# disp.net
KiCad netlist of a schematic drawn in EAGLE
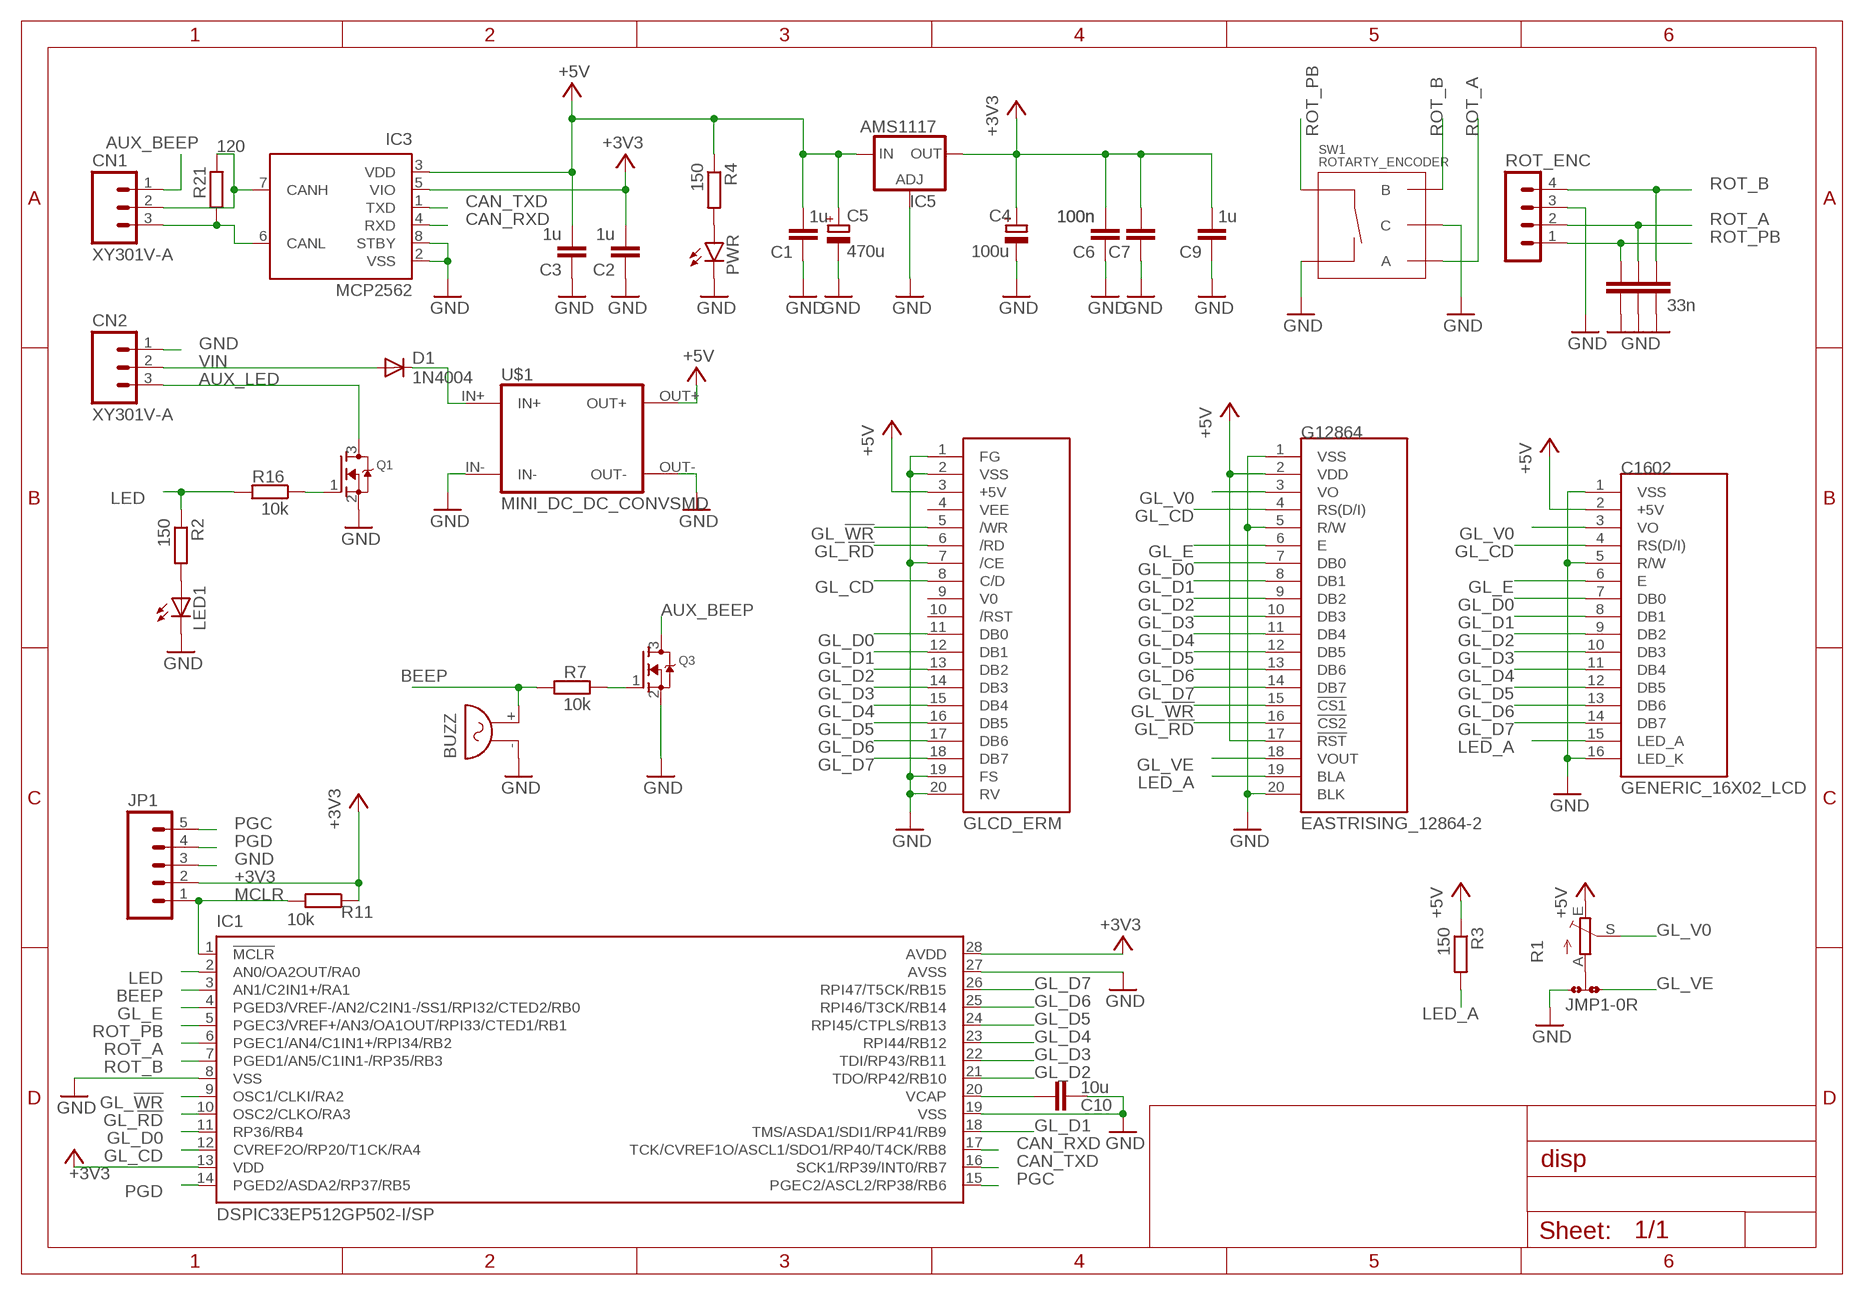
[diagram p0: schematic, sheet 1]

(export (version "E")
  (design (tool "Eeschema 10.0.6"))
  (components
    (comp (ref "BUZZ")
      (value "F/QMX")
      (footprint "eagle-import:F_QMX")
      (libsource (lib "eagle-import") (part "F/QMX"))
    )
    (comp (ref "C1")
      (value "1u")
      (footprint "eagle-import:C0603K")
      (libsource (lib "eagle-import") (part "C-EUC0603K"))
    )
    (comp (ref "C2")
      (value "1u")
      (footprint "eagle-import:C0603K")
      (libsource (lib "eagle-import") (part "C-EUC0603K"))
    )
    (comp (ref "C3")
      (value "1u")
      (footprint "eagle-import:C0603K")
      (libsource (lib "eagle-import") (part "C-EUC0603K"))
    )
    (comp (ref "C4")
      (value "100u")
      (footprint "eagle-import:E2,5-7")
      (libsource (lib "eagle-import") (part "CPOL-EUE2.5-7"))
    )
    (comp (ref "C5")
      (value "470u")
      (footprint "eagle-import:E3,5-8")
      (libsource (lib "eagle-import") (part "CPOL-EUE3.5-8"))
    )
    (comp (ref "C6")
      (value "100n")
      (footprint "eagle-import:C0603K")
      (libsource (lib "eagle-import") (part "C-EUC0603K"))
    )
    (comp (ref "C7")
      (value "100n")
      (footprint "eagle-import:C0603K")
      (libsource (lib "eagle-import") (part "C-EUC0603K"))
    )
    (comp (ref "C9")
      (value "1u")
      (footprint "eagle-import:C0603K")
      (libsource (lib "eagle-import") (part "C-EUC0603K"))
    )
    (comp (ref "C10")
      (value "10u")
      (footprint "eagle-import:C025-030X050")
      (libsource (lib "eagle-import") (part "C-EU025-030X050"))
    )
    (comp (ref "C11")
      (value "33n")
      (footprint "eagle-import:C0603K")
      (libsource (lib "eagle-import") (part "C-EUC0603K"))
    )
    (comp (ref "C12")
      (value "33n")
      (footprint "eagle-import:C0603K")
      (libsource (lib "eagle-import") (part "C-EUC0603K"))
    )
    (comp (ref "C13")
      (value "33n")
      (footprint "eagle-import:C0603K")
      (libsource (lib "eagle-import") (part "C-EUC0603K"))
    )
    (comp (ref "C1602")
      (value "GENERIC_16X02_LCD")
      (footprint "eagle-import:1X16")
      (libsource (lib "eagle-import") (part "GENERIC_16X02_LCD"))
    )
    (comp (ref "CN1")
      (value "XY301V-A")
      (footprint "eagle-import:XY301V-A")
      (libsource (lib "eagle-import") (part "XY301V-A"))
    )
    (comp (ref "CN2")
      (value "XY301V-A")
      (footprint "eagle-import:XY301V-A")
      (libsource (lib "eagle-import") (part "XY301V-A"))
    )
    (comp (ref "D1")
      (value "1N4004")
      (footprint "eagle-import:DO41-10")
      (libsource (lib "eagle-import") (part "1N4004"))
    )
    (comp (ref "G12864")
      (value "EASTRISING_12864-2")
      (footprint "eagle-import:1X20")
      (libsource (lib "eagle-import") (part "EASTRISING_12864-2"))
    )
    (comp (ref "GLCD_ERM")
      (value "WITSCHI_ERM25664AAG-1")
      (footprint "eagle-import:1X20")
      (libsource (lib "eagle-import") (part "WITSCHI_ERM25664AAG-1"))
    )
    (comp (ref "IC1")
      (value "DSPIC33EP512GP502-I/SP")
      (footprint "eagle-import:DIL28-3")
      (libsource (lib "eagle-import") (part "DSPIC33EP512502-I/SPGP"))
    )
    (comp (ref "IC3")
      (value "MCP2562")
      (footprint "eagle-import:DIL8")
      (libsource (lib "eagle-import") (part "MCP2562-E/P"))
    )
    (comp (ref "IC5")
      (value "AMS1117")
      (footprint "eagle-import:SOT223")
      (libsource (lib "eagle-import") (part "LD117A?S33TR"))
    )
    (comp (ref "JMP1")
      (value "0R-JUMPB")
      (footprint "eagle-import:B0R-JMP")
      (libsource (lib "eagle-import") (part "0R-JUMPB"))
    )
    (comp (ref "JP1")
      (value "M05PTH")
      (footprint "eagle-import:1X05")
      (libsource (lib "eagle-import") (part "M05PTH"))
    )
    (comp (ref "LED1")
      (value "LED5MM")
      (footprint "eagle-import:LED5MM")
      (libsource (lib "eagle-import") (part "adafruit_LED5MM"))
    )
    (comp (ref "PWR")
      (value "LED-FKIT-1206")
      (footprint "eagle-import:FKIT-LED-1206")
      (libsource (lib "eagle-import") (part "LED-FKIT-1206"))
    )
    (comp (ref "Q1")
      (value "MOSFET-NREFLOW")
      (footprint "eagle-import:SOT23")
      (libsource (lib "eagle-import") (part "MOSFET-NREFLOW"))
    )
    (comp (ref "Q3")
      (value "MOSFET-NREFLOW")
      (footprint "eagle-import:SOT23")
      (libsource (lib "eagle-import") (part "MOSFET-NREFLOW"))
    )
    (comp (ref "R1")
      (value "TRIM_EU-B64Y")
      (footprint "eagle-import:B64Y")
      (libsource (lib "eagle-import") (part "TRIM_EU-B64Y"))
    )
    (comp (ref "R2")
      (value "150")
      (footprint "eagle-import:R0603")
      (libsource (lib "eagle-import") (part "R-EU_R0603"))
    )
    (comp (ref "R3")
      (value "150")
      (footprint "eagle-import:R0603")
      (libsource (lib "eagle-import") (part "R-EU_R0603"))
    )
    (comp (ref "R4")
      (value "150")
      (footprint "eagle-import:R0603")
      (libsource (lib "eagle-import") (part "R-EU_R0603"))
    )
    (comp (ref "R7")
      (value "10k")
      (footprint "eagle-import:R0603")
      (libsource (lib "eagle-import") (part "R-EU_R0603"))
    )
    (comp (ref "R11")
      (value "10k")
      (footprint "eagle-import:R0603")
      (libsource (lib "eagle-import") (part "R-EU_R0603"))
    )
    (comp (ref "R16")
      (value "10k")
      (footprint "eagle-import:R0603")
      (libsource (lib "eagle-import") (part "R-EU_R0603"))
    )
    (comp (ref "R21")
      (value "120")
      (footprint "eagle-import:R0603")
      (libsource (lib "eagle-import") (part "R-EU_R0603"))
    )
    (comp (ref "ROT_ENC")
      (value "MA04-1")
      (footprint "eagle-import:MA04-1")
      (libsource (lib "eagle-import") (part "MA04-1"))
    )
    (comp (ref "SW1")
      (value "ROTARTY_ENCODER")
      (footprint "eagle-import:ROTARY_ENC_PLAIN")
      (libsource (lib "eagle-import") (part "ROTARTY_ENCODER"))
    )
    (comp (ref "U$1")
      (value "MINI_DC_DC_CONVSMD")
      (footprint "eagle-import:DSN-MINI-360-SMD")
      (libsource (lib "eagle-import") (part "MINI_DC_DC_CONVSMD"))
    )
  )
  (nets
    (net (code "1") (name "+3V3") (class "Default")
      (node (ref "C2") (pin "2") (pinfunction "2_2") (pintype "passive"))
      (node (ref "C4") (pin "+") (pinfunction "+_+") (pintype "passive"))
      (node (ref "C6") (pin "2") (pinfunction "2_2") (pintype "passive"))
      (node (ref "C7") (pin "2") (pinfunction "2_2") (pintype "passive"))
      (node (ref "C9") (pin "2") (pinfunction "2_2") (pintype "passive"))
      (node (ref "IC1") (pin "13") (pinfunction "VDD_13") (pintype "power_in"))
      (node (ref "IC1") (pin "28") (pinfunction "AVDD_28") (pintype "power_in"))
      (node (ref "IC3") (pin "5") (pinfunction "VIO_5") (pintype "power_in"))
      (node (ref "IC5") (pin "2") (pinfunction "OUT_2") (pintype "passive"))
      (node (ref "IC5") (pin "@2") (pinfunction "OUT_@2") (pintype "passive"))
      (node (ref "JP1") (pin "2") (pinfunction "2_2") (pintype "passive"))
      (node (ref "R11") (pin "1") (pinfunction "1_1") (pintype "passive"))
    )
    (net (code "2") (name "+5V") (class "Default")
      (node (ref "C1") (pin "2") (pinfunction "2_2") (pintype "passive"))
      (node (ref "C1602") (pin "2") (pinfunction "+5V_2") (pintype "power_in"))
      (node (ref "C3") (pin "2") (pinfunction "2_2") (pintype "passive"))
      (node (ref "C5") (pin "+") (pinfunction "+_+") (pintype "passive"))
      (node (ref "G12864") (pin "17") (pinfunction "~{RST}_17") (pintype "input"))
      (node (ref "G12864") (pin "2") (pinfunction "VDD_2") (pintype "power_in"))
      (node (ref "GLCD_ERM") (pin "3") (pinfunction "+5V_3") (pintype "power_in"))
      (node (ref "IC3") (pin "3") (pinfunction "VDD_3") (pintype "power_in"))
      (node (ref "IC5") (pin "3") (pinfunction "IN_3") (pintype "input"))
      (node (ref "R1") (pin "E") (pinfunction "E_E") (pintype "passive"))
      (node (ref "R3") (pin "1") (pinfunction "1_1") (pintype "passive"))
      (node (ref "R4") (pin "1") (pinfunction "1_1") (pintype "passive"))
      (node (ref "U$1") (pin "OUT+") (pinfunction "OUT+_OUT+") (pintype "output"))
    )
    (net (code "3") (name "/AUX_BEEP") (class "Default")
      (node (ref "CN1") (pin "1") (pinfunction "1_1") (pintype "passive"))
      (node (ref "Q3") (pin "3") (pinfunction "D_3") (pintype "bidirectional"))
    )
    (net (code "4") (name "/AUX_LED") (class "Default")
      (node (ref "CN2") (pin "3") (pinfunction "3_3") (pintype "passive"))
      (node (ref "Q1") (pin "3") (pinfunction "D_3") (pintype "bidirectional"))
    )
    (net (code "5") (name "/BEEP") (class "Default")
      (node (ref "BUZZ") (pin "+") (pinfunction "2_+") (pintype "passive"))
      (node (ref "IC1") (pin "3") (pinfunction "AN1/C2IN1+/RA1_3") (pintype "bidirectional"))
      (node (ref "R7") (pin "2") (pinfunction "2_2") (pintype "passive"))
    )
    (net (code "6") (name "/CAN_RXD") (class "Default")
      (node (ref "IC1") (pin "17") (pinfunction "TCK/CVREF1O/ASCL1/SDO1/RP40/T4CK/RB8_17") (pintype "bidirectional"))
      (node (ref "IC3") (pin "4") (pinfunction "RXD_4") (pintype "output"))
    )
    (net (code "7") (name "/CAN_TXD") (class "Default")
      (node (ref "IC1") (pin "16") (pinfunction "SCK1/RP39/INT0/RB7_16") (pintype "bidirectional"))
      (node (ref "IC3") (pin "1") (pinfunction "TXD_1") (pintype "input"))
    )
    (net (code "8") (name "/GL_CD") (class "Default")
      (node (ref "C1602") (pin "4") (pinfunction "RS(D/I)_4") (pintype "input"))
      (node (ref "G12864") (pin "4") (pinfunction "RS(D/I)_4") (pintype "input"))
      (node (ref "GLCD_ERM") (pin "8") (pinfunction "C/D_8") (pintype "input"))
      (node (ref "IC1") (pin "12") (pinfunction "CVREF2O/RP20/T1CK/RA4_12") (pintype "bidirectional"))
    )
    (net (code "9") (name "/GL_D0") (class "Default")
      (node (ref "C1602") (pin "7") (pinfunction "DB0_7") (pintype "bidirectional"))
      (node (ref "G12864") (pin "7") (pinfunction "DB0_7") (pintype "bidirectional"))
      (node (ref "GLCD_ERM") (pin "11") (pinfunction "DB0_11") (pintype "bidirectional"))
      (node (ref "IC1") (pin "11") (pinfunction "RP36/RB4_11") (pintype "bidirectional"))
    )
    (net (code "10") (name "/GL_D1") (class "Default")
      (node (ref "C1602") (pin "8") (pinfunction "DB1_8") (pintype "bidirectional"))
      (node (ref "G12864") (pin "8") (pinfunction "DB1_8") (pintype "bidirectional"))
      (node (ref "GLCD_ERM") (pin "12") (pinfunction "DB1_12") (pintype "bidirectional"))
      (node (ref "IC1") (pin "18") (pinfunction "TMS/ASDA1/SDI1/RP41/RB9_18") (pintype "bidirectional"))
    )
    (net (code "11") (name "/GL_D2") (class "Default")
      (node (ref "C1602") (pin "9") (pinfunction "DB2_9") (pintype "bidirectional"))
      (node (ref "G12864") (pin "9") (pinfunction "DB2_9") (pintype "bidirectional"))
      (node (ref "GLCD_ERM") (pin "13") (pinfunction "DB2_13") (pintype "bidirectional"))
      (node (ref "IC1") (pin "21") (pinfunction "TDO/RP42/RB10_21") (pintype "bidirectional"))
    )
    (net (code "12") (name "/GL_D3") (class "Default")
      (node (ref "C1602") (pin "10") (pinfunction "DB3_10") (pintype "bidirectional"))
      (node (ref "G12864") (pin "10") (pinfunction "DB3_10") (pintype "bidirectional"))
      (node (ref "GLCD_ERM") (pin "14") (pinfunction "DB3_14") (pintype "bidirectional"))
      (node (ref "IC1") (pin "22") (pinfunction "TDI/RP43/RB11_22") (pintype "bidirectional"))
    )
    (net (code "13") (name "/GL_D4") (class "Default")
      (node (ref "C1602") (pin "11") (pinfunction "DB4_11") (pintype "bidirectional"))
      (node (ref "G12864") (pin "11") (pinfunction "DB4_11") (pintype "bidirectional"))
      (node (ref "GLCD_ERM") (pin "15") (pinfunction "DB4_15") (pintype "bidirectional"))
      (node (ref "IC1") (pin "23") (pinfunction "RPI44/RB12_23") (pintype "bidirectional"))
    )
    (net (code "14") (name "/GL_D5") (class "Default")
      (node (ref "C1602") (pin "12") (pinfunction "DB5_12") (pintype "bidirectional"))
      (node (ref "G12864") (pin "12") (pinfunction "DB5_12") (pintype "bidirectional"))
      (node (ref "GLCD_ERM") (pin "16") (pinfunction "DB5_16") (pintype "bidirectional"))
      (node (ref "IC1") (pin "24") (pinfunction "RPI45/CTPLS/RB13_24") (pintype "bidirectional"))
    )
    (net (code "15") (name "/GL_D6") (class "Default")
      (node (ref "C1602") (pin "13") (pinfunction "DB6_13") (pintype "bidirectional"))
      (node (ref "G12864") (pin "13") (pinfunction "DB6_13") (pintype "bidirectional"))
      (node (ref "GLCD_ERM") (pin "17") (pinfunction "DB6_17") (pintype "bidirectional"))
      (node (ref "IC1") (pin "25") (pinfunction "RPI46/T3CK/RB14_25") (pintype "bidirectional"))
    )
    (net (code "16") (name "/GL_D7") (class "Default")
      (node (ref "C1602") (pin "14") (pinfunction "DB7_14") (pintype "bidirectional"))
      (node (ref "G12864") (pin "14") (pinfunction "DB7_14") (pintype "bidirectional"))
      (node (ref "GLCD_ERM") (pin "18") (pinfunction "DB7_18") (pintype "bidirectional"))
      (node (ref "IC1") (pin "26") (pinfunction "RPI47/T5CK/RB15_26") (pintype "bidirectional"))
    )
    (net (code "17") (name "/GL_E") (class "Default")
      (node (ref "C1602") (pin "6") (pinfunction "E_6") (pintype "input"))
      (node (ref "G12864") (pin "6") (pinfunction "E_6") (pintype "input"))
      (node (ref "IC1") (pin "4") (pinfunction "PGED3/VREF-/AN2/C2IN1-/SS1/RPI32/CTED2/RB0_4") (pintype "bidirectional"))
    )
    (net (code "18") (name "/GL_V0") (class "Default")
      (node (ref "C1602") (pin "3") (pinfunction "VO_3") (pintype "bidirectional"))
      (node (ref "G12864") (pin "3") (pinfunction "VO_3") (pintype "bidirectional"))
      (node (ref "R1") (pin "S") (pinfunction "S_S") (pintype "passive"))
    )
    (net (code "19") (name "/GL_VE") (class "Default")
      (node (ref "G12864") (pin "18") (pinfunction "VOUT_18") (pintype "bidirectional"))
      (node (ref "JMP1") (pin "3") (pinfunction "3_3") (pintype "passive"))
    )
    (net (code "20") (name "/GL_~{RD}") (class "Default")
      (node (ref "G12864") (pin "16") (pinfunction "~{CS2}_16") (pintype "input"))
      (node (ref "GLCD_ERM") (pin "6") (pinfunction "/RD_6") (pintype "input"))
      (node (ref "IC1") (pin "10") (pinfunction "OSC2/CLKO/RA3_10") (pintype "bidirectional"))
    )
    (net (code "21") (name "/GL_~{WR}") (class "Default")
      (node (ref "G12864") (pin "15") (pinfunction "~{CS1}_15") (pintype "input"))
      (node (ref "GLCD_ERM") (pin "5") (pinfunction "/WR_5") (pintype "input"))
      (node (ref "IC1") (pin "9") (pinfunction "OSC1/CLKI/RA2_9") (pintype "input"))
    )
    (net (code "22") (name "/LED") (class "Default")
      (node (ref "IC1") (pin "2") (pinfunction "AN0/OA2OUT/RA0_2") (pintype "bidirectional"))
      (node (ref "R16") (pin "2") (pinfunction "2_2") (pintype "passive"))
      (node (ref "R2") (pin "1") (pinfunction "1_1") (pintype "passive"))
    )
    (net (code "23") (name "/LED_A") (class "Default")
      (node (ref "C1602") (pin "15") (pinfunction "LED_A_15") (pintype "power_in"))
      (node (ref "G12864") (pin "19") (pinfunction "BLA_19") (pintype "passive"))
      (node (ref "R3") (pin "2") (pinfunction "2_2") (pintype "passive"))
    )
    (net (code "24") (name "/MCLR") (class "Default")
      (node (ref "IC1") (pin "1") (pinfunction "~{MCLR}_1") (pintype "input"))
      (node (ref "JP1") (pin "1") (pinfunction "1_1") (pintype "passive"))
      (node (ref "R11") (pin "2") (pinfunction "2_2") (pintype "passive"))
    )
    (net (code "25") (name "/PGC") (class "Default")
      (node (ref "IC1") (pin "15") (pinfunction "PGEC2/ASCL2/RP38/RB6_15") (pintype "bidirectional"))
      (node (ref "JP1") (pin "5") (pinfunction "5_5") (pintype "passive"))
    )
    (net (code "26") (name "/PGD") (class "Default")
      (node (ref "IC1") (pin "14") (pinfunction "PGED2/ASDA2/RP37/RB5_14") (pintype "bidirectional"))
      (node (ref "JP1") (pin "4") (pinfunction "4_4") (pintype "passive"))
    )
    (net (code "27") (name "/ROT_A") (class "Default")
      (node (ref "C12") (pin "2") (pinfunction "2_2") (pintype "passive"))
      (node (ref "IC1") (pin "6") (pinfunction "PGEC1/AN4/C1IN1+/RPI34/RB2_6") (pintype "bidirectional"))
      (node (ref "ROT_ENC") (pin "2") (pinfunction "2_2") (pintype "passive"))
      (node (ref "SW1") (pin "A") (pinfunction "A_A") (pintype "bidirectional"))
    )
    (net (code "28") (name "/ROT_B") (class "Default")
      (node (ref "C13") (pin "2") (pinfunction "2_2") (pintype "passive"))
      (node (ref "IC1") (pin "7") (pinfunction "PGED1/AN5/C1IN1-/RP35/RB3_7") (pintype "bidirectional"))
      (node (ref "ROT_ENC") (pin "4") (pinfunction "4_4") (pintype "passive"))
      (node (ref "SW1") (pin "B") (pinfunction "B_B") (pintype "bidirectional"))
    )
    (net (code "29") (name "/ROT_PB") (class "Default")
      (node (ref "C11") (pin "2") (pinfunction "2_2") (pintype "passive"))
      (node (ref "IC1") (pin "5") (pinfunction "PGEC3/VREF+/AN3/OA1OUT/RPI33/CTED1/RB1_5") (pintype "bidirectional"))
      (node (ref "ROT_ENC") (pin "1") (pinfunction "1_1") (pintype "passive"))
      (node (ref "SW1") (pin "SW+") (pinfunction "SW+_SW+") (pintype "bidirectional"))
    )
    (net (code "30") (name "/V0") (class "Default")
      (node (ref "GLCD_ERM") (pin "9") (pinfunction "V0_9") (pintype "power_in"))
    )
    (net (code "31") (name "/VEE") (class "Default")
      (node (ref "GLCD_ERM") (pin "4") (pinfunction "VEE_4") (pintype "power_in"))
    )
    (net (code "32") (name "/VIN") (class "Default")
      (node (ref "CN2") (pin "2") (pinfunction "2_2") (pintype "passive"))
      (node (ref "D1") (pin "A") (pinfunction "A_A") (pintype "passive"))
    )
    (net (code "33") (name "GND") (class "Default")
      (node (ref "BUZZ") (pin "-") (pinfunction "1_-") (pintype "passive"))
      (node (ref "C1") (pin "1") (pinfunction "1_1") (pintype "passive"))
      (node (ref "C10") (pin "1") (pinfunction "1_1") (pintype "passive"))
      (node (ref "C11") (pin "1") (pinfunction "1_1") (pintype "passive"))
      (node (ref "C12") (pin "1") (pinfunction "1_1") (pintype "passive"))
      (node (ref "C13") (pin "1") (pinfunction "1_1") (pintype "passive"))
      (node (ref "C1602") (pin "1") (pinfunction "VSS_1") (pintype "power_in"))
      (node (ref "C1602") (pin "16") (pinfunction "LED_K_16") (pintype "power_in"))
      (node (ref "C1602") (pin "5") (pinfunction "R/W_5") (pintype "input"))
      (node (ref "C2") (pin "1") (pinfunction "1_1") (pintype "passive"))
      (node (ref "C3") (pin "1") (pinfunction "1_1") (pintype "passive"))
      (node (ref "C4") (pin "-") (pinfunction "-_-") (pintype "passive"))
      (node (ref "C5") (pin "-") (pinfunction "-_-") (pintype "passive"))
      (node (ref "C6") (pin "1") (pinfunction "1_1") (pintype "passive"))
      (node (ref "C7") (pin "1") (pinfunction "1_1") (pintype "passive"))
      (node (ref "C9") (pin "1") (pinfunction "1_1") (pintype "passive"))
      (node (ref "CN2") (pin "1") (pinfunction "1_1") (pintype "passive"))
      (node (ref "G12864") (pin "1") (pinfunction "VSS_1") (pintype "power_in"))
      (node (ref "G12864") (pin "20") (pinfunction "BLK_20") (pintype "passive"))
      (node (ref "G12864") (pin "5") (pinfunction "R/W_5") (pintype "input"))
      (node (ref "GLCD_ERM") (pin "1") (pinfunction "FG_1") (pintype "power_in"))
      (node (ref "GLCD_ERM") (pin "19") (pinfunction "FS_19") (pintype "bidirectional"))
      (node (ref "GLCD_ERM") (pin "2") (pinfunction "VSS_2") (pintype "power_in"))
      (node (ref "GLCD_ERM") (pin "20") (pinfunction "RV_20") (pintype "bidirectional"))
      (node (ref "GLCD_ERM") (pin "7") (pinfunction "/CE_7") (pintype "input"))
      (node (ref "IC1") (pin "19") (pinfunction "VSS_19") (pintype "power_in"))
      (node (ref "IC1") (pin "27") (pinfunction "AVSS_27") (pintype "power_in"))
      (node (ref "IC1") (pin "8") (pinfunction "VSS_8") (pintype "power_in"))
      (node (ref "IC3") (pin "2") (pinfunction "VSS_2") (pintype "power_in"))
      (node (ref "IC3") (pin "8") (pinfunction "STBY_8") (pintype "input"))
      (node (ref "IC5") (pin "1") (pinfunction "ADJ_1") (pintype "input"))
      (node (ref "JMP1") (pin "1") (pinfunction "1_1") (pintype "passive"))
      (node (ref "JP1") (pin "3") (pinfunction "3_3") (pintype "passive"))
      (node (ref "LED1") (pin "K") (pinfunction "C_K") (pintype "passive"))
      (node (ref "PWR") (pin "C") (pinfunction "C_C") (pintype "passive"))
      (node (ref "Q1") (pin "2") (pinfunction "S_2") (pintype "bidirectional"))
      (node (ref "Q3") (pin "2") (pinfunction "S_2") (pintype "bidirectional"))
      (node (ref "ROT_ENC") (pin "3") (pinfunction "3_3") (pintype "passive"))
      (node (ref "SW1") (pin "C") (pinfunction "C_C") (pintype "bidirectional"))
      (node (ref "SW1") (pin "SW-") (pinfunction "SW-_SW-") (pintype "bidirectional"))
      (node (ref "U$1") (pin "IN-") (pinfunction "IN-_IN-") (pintype "power_in"))
      (node (ref "U$1") (pin "OUT-") (pinfunction "OUT-_OUT-") (pintype "power_in"))
    )
    (net (code "34") (name "Net-(D1-PadC)") (class "Default")
      (node (ref "D1") (pin "C") (pinfunction "C_C") (pintype "passive"))
      (node (ref "U$1") (pin "IN+") (pinfunction "IN+_IN+") (pintype "input"))
    )
    (net (code "35") (name "Net-(IC1-VCAP)") (class "Default")
      (node (ref "C10") (pin "2") (pinfunction "2_2") (pintype "passive"))
      (node (ref "IC1") (pin "20") (pinfunction "VCAP_20") (pintype "power_in"))
    )
    (net (code "36") (name "Net-(IC3-CANH)") (class "Default")
      (node (ref "CN1") (pin "2") (pinfunction "2_2") (pintype "passive"))
      (node (ref "IC3") (pin "7") (pinfunction "CANH_7") (pintype "bidirectional"))
      (node (ref "R21") (pin "2") (pinfunction "2_2") (pintype "passive"))
    )
    (net (code "37") (name "Net-(IC3-CANL)") (class "Default")
      (node (ref "CN1") (pin "3") (pinfunction "3_3") (pintype "passive"))
      (node (ref "IC3") (pin "6") (pinfunction "CANL_6") (pintype "bidirectional"))
      (node (ref "R21") (pin "1") (pinfunction "1_1") (pintype "passive"))
    )
    (net (code "38") (name "Net-(JMP1-Pad2)") (class "Default")
      (node (ref "JMP1") (pin "2") (pinfunction "2_2") (pintype "passive"))
      (node (ref "R1") (pin "A") (pinfunction "A_A") (pintype "passive"))
    )
    (net (code "39") (name "Net-(LED1-PadA)") (class "Default")
      (node (ref "LED1") (pin "A") (pinfunction "A_A") (pintype "passive"))
      (node (ref "R2") (pin "2") (pinfunction "2_2") (pintype "passive"))
    )
    (net (code "40") (name "Net-(PWR-PadA)") (class "Default")
      (node (ref "PWR") (pin "A") (pinfunction "A_A") (pintype "passive"))
      (node (ref "R4") (pin "2") (pinfunction "2_2") (pintype "passive"))
    )
    (net (code "41") (name "Net-(Q1-G)") (class "Default")
      (node (ref "Q1") (pin "1") (pinfunction "G_1") (pintype "bidirectional"))
      (node (ref "R16") (pin "1") (pinfunction "1_1") (pintype "passive"))
    )
    (net (code "42") (name "Net-(Q3-G)") (class "Default")
      (node (ref "Q3") (pin "1") (pinfunction "G_1") (pintype "bidirectional"))
      (node (ref "R7") (pin "1") (pinfunction "1_1") (pintype "passive"))
    )
    (net (code "43") (name "unconnected-(GLCD_ERM-{slash}RST-Pad10)") (class "Default")
      (node (ref "GLCD_ERM") (pin "10") (pinfunction "/RST_10") (pintype "input"))
    )
  )
)
